# PCB_IGEM.net
KiCad netlist of a schematic drawn in EasyEDA Pro
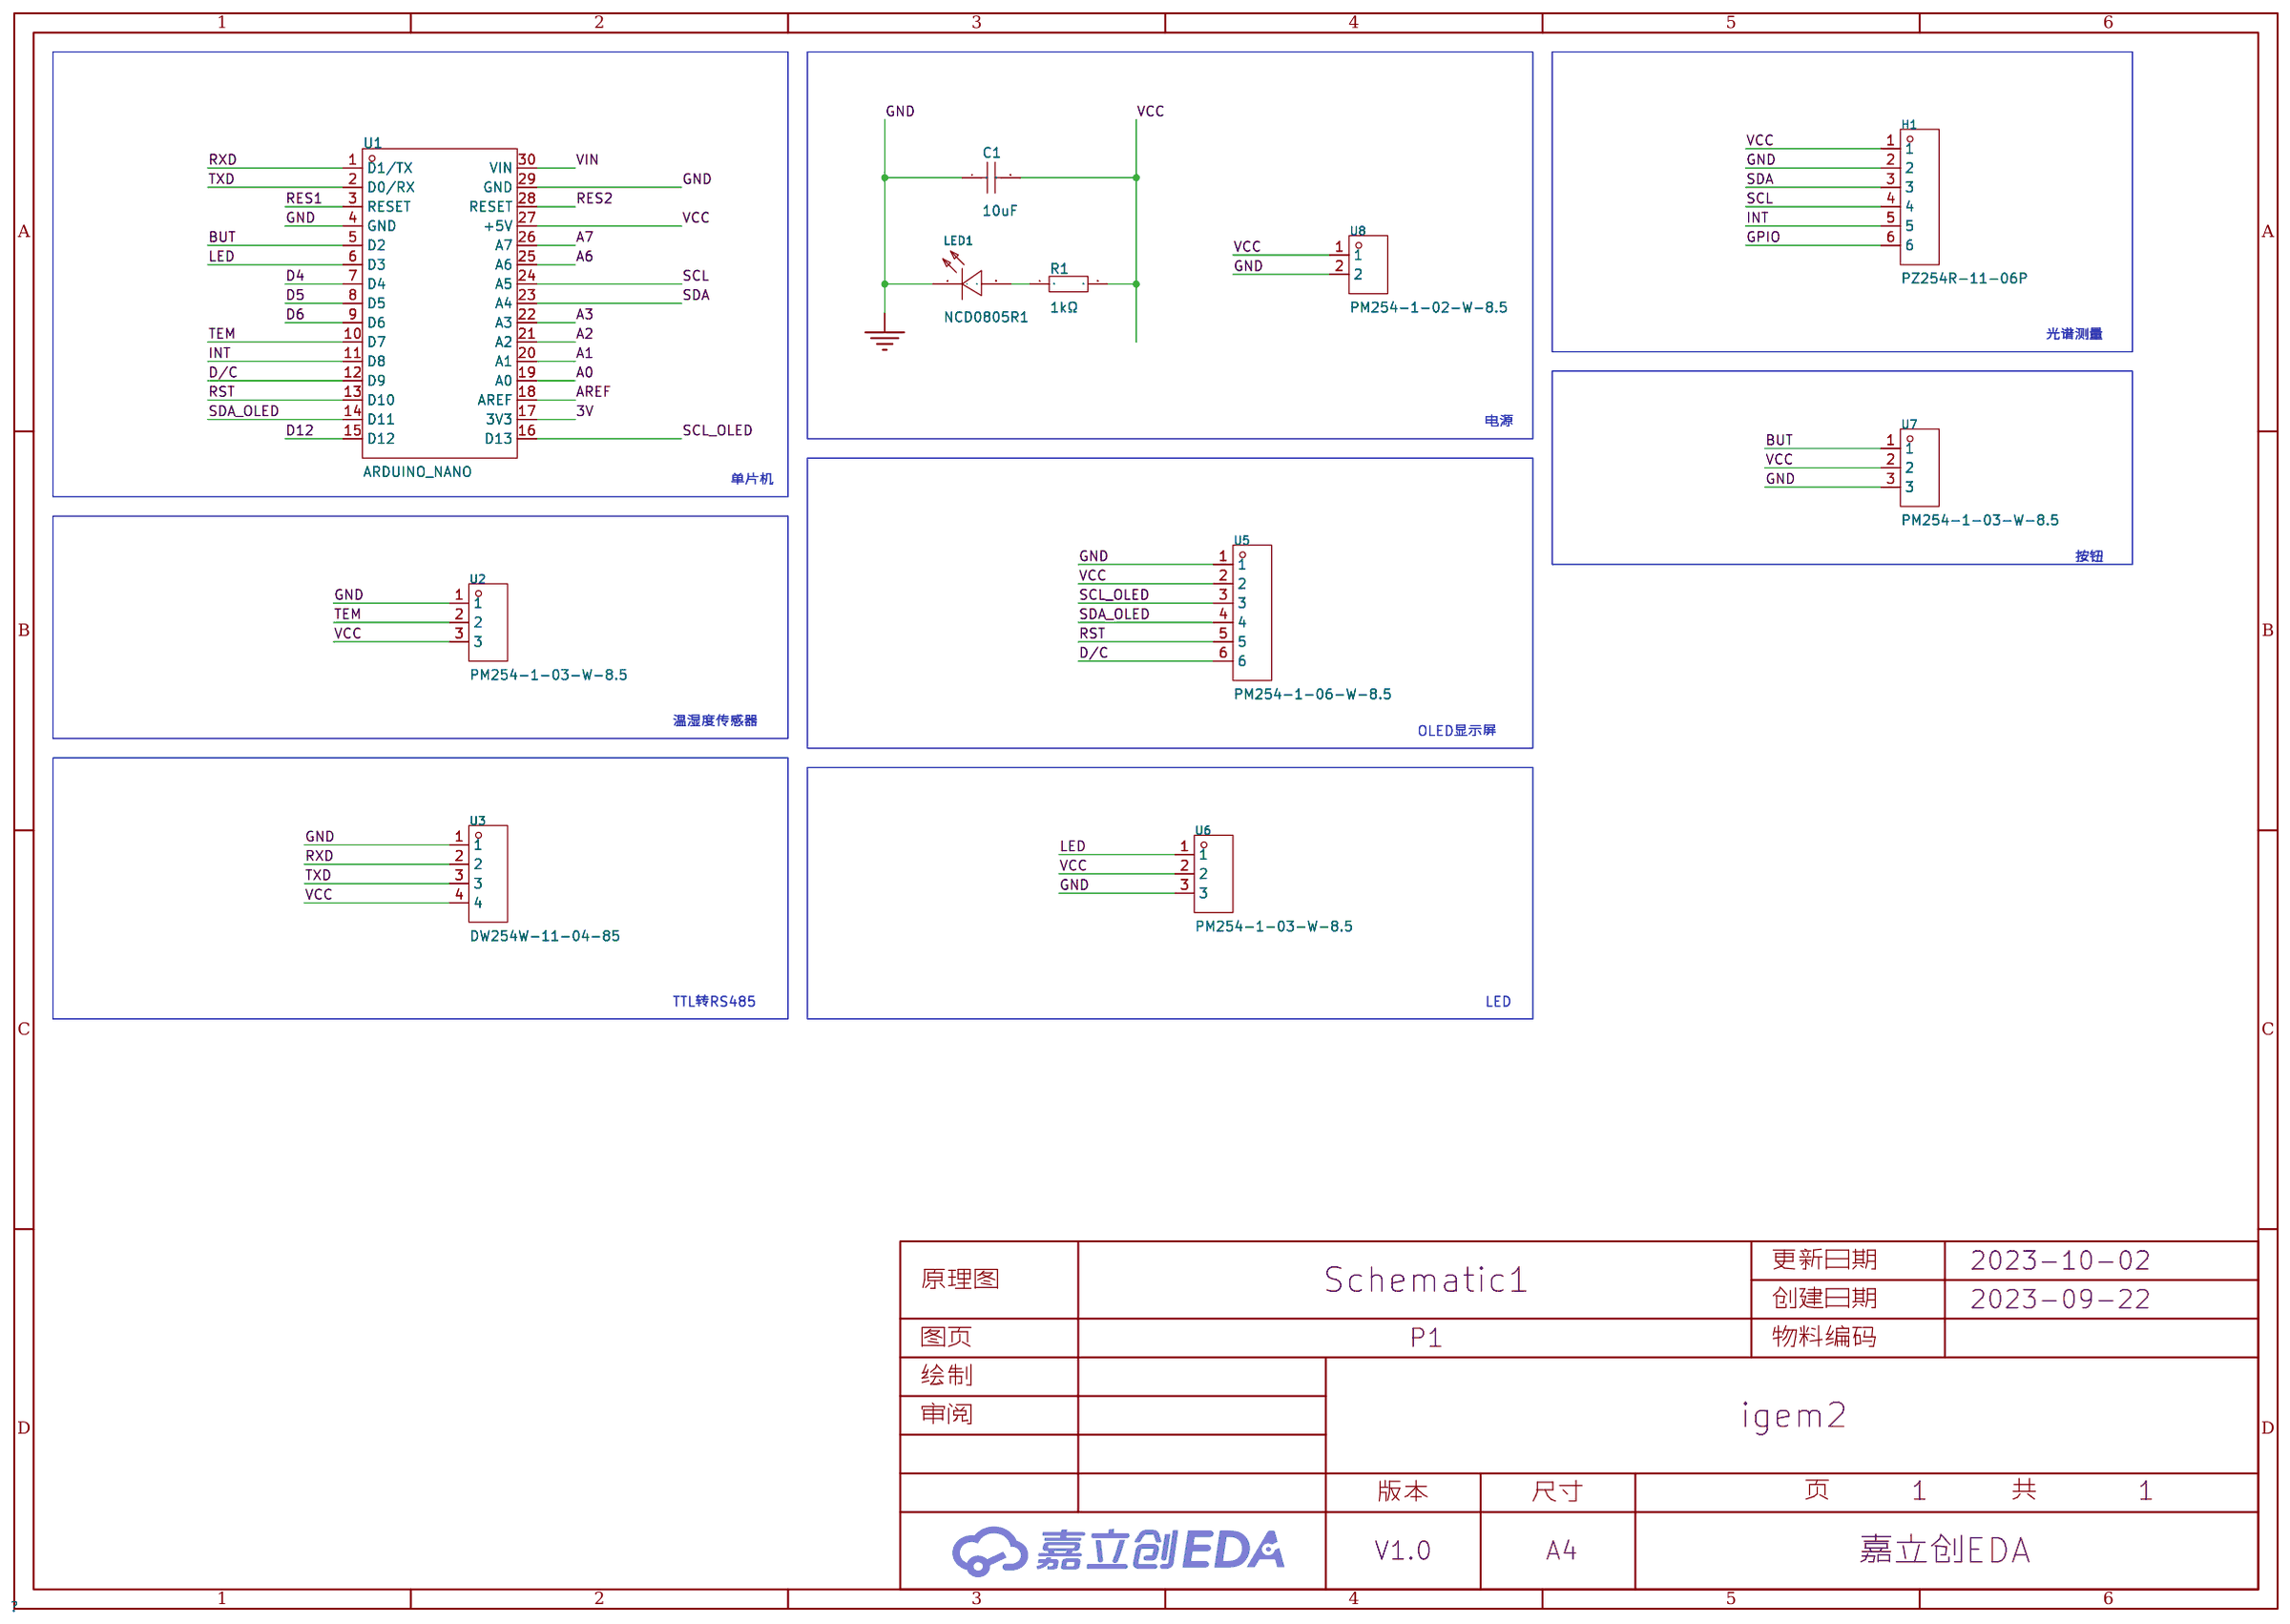
[diagram p0: schematic sheet]

(export (version "E")
  (design (tool "Eeschema 10.0.6"))
  (components
    (comp (ref "C1")
      (value "10uF")
      (footprint "easyedapro:C0805")
      (description "容值:10uF;精度:±10%;额定电压:25V;材质(温度系数):X5R;")
      (fields
        (field (name "Manufacturer Part") "CL21A106KAYNNNE")
        (field (name "Manufacturer") "SAMSUNG(三星)")
      )
      (libsource (lib "easyedapro") (part "CL21A106KAYNNNE"))
    )
    (comp (ref "H1")
      (value "PZ254R-11-06P")
      (footprint "easyedapro:HDR-TH_6P-P2.54-H-M-W10.4")
      (fields (field (name "Manufacturer") "XFCN(兴飞)"))
      (libsource (lib "easyedapro") (part "PZ254R-11-06P"))
    )
    (comp (ref "LED1")
      (value "NCD0805R1")
      (footprint "easyedapro:LED0805-RD_RED")
      (description "发光颜色:红灯;")
      (fields (field (name "Manufacturer") "国星光电"))
      (libsource (lib "easyedapro") (part "FC-2012HRK-620D"))
    )
    (comp (ref "R1")
      (value "1kΩ")
      (footprint "easyedapro:R0805")
      (description "电阻类型:厚膜电阻;阻值:1kΩ;精度:±1%;功率:125mW;")
      (fields
        (field (name "Manufacturer Part") "0805W8F1001T5E")
        (field (name "Manufacturer") "UNI-ROYAL(厚声)")
      )
      (libsource (lib "easyedapro") (part "0805W8F1001T5E"))
    )
    (comp (ref "U1")
      (value "ARDUINO_NANO")
      (footprint "easyedapro:COMM-TH_ARDUINO_NANO")
      (libsource (lib "easyedapro") (part "ARDUINO_NANO"))
    )
    (comp (ref "U2")
      (value "PM254-1-03-W-8.5")
      (footprint "easyedapro:HDR-TH_3P-P2.54-H-F-W10.0-N")
      (fields (field (name "Manufacturer") "HCTL(华灿天禄)"))
      (libsource (lib "easyedapro") (part "PM254-1-03-W-8.5"))
    )
    (comp (ref "U3")
      (value "DW254W-11-04-85")
      (footprint "easyedapro:HDR-TH_4P-P2.54-H-F-W10.3-N")
      (description "排数:单排;总孔位数:4P;间距:2.54mm;插孔结构:1x4P;行距:-;安装类型:弯插;圆孔/方孔:方孔;额定电流:3A;额定电压:-;插孔方向:侧面;塑高:8.5mm;工作温度范围:-;")
      (fields (field (name "Manufacturer") "DEALON(德艺隆)"))
      (libsource (lib "easyedapro") (part "DW254W-11-04-85"))
    )
    (comp (ref "U5")
      (value "PM254-1-06-W-8.5")
      (footprint "easyedapro:HDR-TH_6P-P2.54-H-F-W10.0-N")
      (fields (field (name "Manufacturer") "HCTL(华灿天禄)"))
      (libsource (lib "easyedapro") (part "PM254-1-06-W-8.5"))
    )
    (comp (ref "U6")
      (value "PM254-1-03-W-8.5")
      (footprint "easyedapro:HDR-TH_3P-P2.54-H-F-W10.0-N")
      (fields (field (name "Manufacturer") "HCTL(华灿天禄)"))
      (libsource (lib "easyedapro") (part "PM254-1-03-W-8.5"))
    )
    (comp (ref "U7")
      (value "PM254-1-03-W-8.5")
      (footprint "easyedapro:HDR-TH_3P-P2.54-H-F-W10.0-N")
      (fields (field (name "Manufacturer") "HCTL(华灿天禄)"))
      (libsource (lib "easyedapro") (part "PM254-1-03-W-8.5"))
    )
    (comp (ref "U8")
      (value "PM254-1-02-W-8.5")
      (footprint "easyedapro:HDR-TH_2P-P2.54-H-F-W10.0-N")
      (fields (field (name "Manufacturer") "HCTL(华灿天禄)"))
      (libsource (lib "easyedapro") (part "PM254-1-02-W-8.5"))
    )
  )
  (nets
    (net (code "1") (name "/3V") (class "Default")
      (node (ref "U1") (pin "17") (pinfunction "3V3_17") (pintype "input"))
    )
    (net (code "2") (name "/A0") (class "Default")
      (node (ref "U1") (pin "19") (pinfunction "A0_19") (pintype "input"))
    )
    (net (code "3") (name "/A1") (class "Default")
      (node (ref "U1") (pin "20") (pinfunction "A1_20") (pintype "input"))
    )
    (net (code "4") (name "/A2") (class "Default")
      (node (ref "U1") (pin "21") (pinfunction "A2_21") (pintype "input"))
    )
    (net (code "5") (name "/A3") (class "Default")
      (node (ref "U1") (pin "22") (pinfunction "A3_22") (pintype "input"))
    )
    (net (code "6") (name "/A6") (class "Default")
      (node (ref "U1") (pin "25") (pinfunction "A6_25") (pintype "input"))
    )
    (net (code "7") (name "/A7") (class "Default")
      (node (ref "U1") (pin "26") (pinfunction "A7_26") (pintype "input"))
    )
    (net (code "8") (name "/AREF") (class "Default")
      (node (ref "U1") (pin "18") (pinfunction "AREF_18") (pintype "input"))
    )
    (net (code "9") (name "/BUT") (class "Default")
      (node (ref "U1") (pin "5") (pinfunction "D2_5") (pintype "input"))
      (node (ref "U7") (pin "1") (pinfunction "1_1") (pintype "input"))
    )
    (net (code "10") (name "/D4") (class "Default")
      (node (ref "U1") (pin "7") (pinfunction "D4_7") (pintype "input"))
    )
    (net (code "11") (name "/D5") (class "Default")
      (node (ref "U1") (pin "8") (pinfunction "D5_8") (pintype "input"))
    )
    (net (code "12") (name "/D6") (class "Default")
      (node (ref "U1") (pin "9") (pinfunction "D6_9") (pintype "input"))
    )
    (net (code "13") (name "/D12") (class "Default")
      (node (ref "U1") (pin "15") (pinfunction "D12_15") (pintype "input"))
    )
    (net (code "14") (name "/D{slash}C") (class "Default")
      (node (ref "U1") (pin "12") (pinfunction "D9_12") (pintype "input"))
      (node (ref "U5") (pin "6") (pinfunction "6_6") (pintype "input"))
    )
    (net (code "15") (name "/GPIO") (class "Default")
      (node (ref "H1") (pin "6") (pinfunction "6_6") (pintype "input"))
    )
    (net (code "16") (name "/INT") (class "Default")
      (node (ref "H1") (pin "5") (pinfunction "5_5") (pintype "input"))
      (node (ref "U1") (pin "11") (pinfunction "D8_11") (pintype "input"))
    )
    (net (code "17") (name "/LED") (class "Default")
      (node (ref "U1") (pin "6") (pinfunction "D3_6") (pintype "input"))
      (node (ref "U6") (pin "1") (pinfunction "1_1") (pintype "input"))
    )
    (net (code "18") (name "/RES1") (class "Default")
      (node (ref "U1") (pin "3") (pinfunction "RESET_3") (pintype "input"))
    )
    (net (code "19") (name "/RES2") (class "Default")
      (node (ref "U1") (pin "28") (pinfunction "RESET_28") (pintype "input"))
    )
    (net (code "20") (name "/RST") (class "Default")
      (node (ref "U1") (pin "13") (pinfunction "D10_13") (pintype "input"))
      (node (ref "U5") (pin "5") (pinfunction "5_5") (pintype "input"))
    )
    (net (code "21") (name "/RXD") (class "Default")
      (node (ref "U1") (pin "1") (pinfunction "D1/TX_1") (pintype "input"))
      (node (ref "U3") (pin "2") (pinfunction "2_2") (pintype "input"))
    )
    (net (code "22") (name "/SCL") (class "Default")
      (node (ref "H1") (pin "4") (pinfunction "4_4") (pintype "input"))
      (node (ref "U1") (pin "24") (pinfunction "A5_24") (pintype "input"))
    )
    (net (code "23") (name "/SCL_OLED") (class "Default")
      (node (ref "U1") (pin "16") (pinfunction "D13_16") (pintype "input"))
      (node (ref "U5") (pin "3") (pinfunction "3_3") (pintype "input"))
    )
    (net (code "24") (name "/SDA") (class "Default")
      (node (ref "H1") (pin "3") (pinfunction "3_3") (pintype "input"))
      (node (ref "U1") (pin "23") (pinfunction "A4_23") (pintype "input"))
    )
    (net (code "25") (name "/SDA_OLED") (class "Default")
      (node (ref "U1") (pin "14") (pinfunction "D11_14") (pintype "input"))
      (node (ref "U5") (pin "4") (pinfunction "4_4") (pintype "input"))
    )
    (net (code "26") (name "/TEM") (class "Default")
      (node (ref "U1") (pin "10") (pinfunction "D7_10") (pintype "input"))
      (node (ref "U2") (pin "2") (pinfunction "2_2") (pintype "input"))
    )
    (net (code "27") (name "/TXD") (class "Default")
      (node (ref "U1") (pin "2") (pinfunction "D0/RX_2") (pintype "input"))
      (node (ref "U3") (pin "3") (pinfunction "3_3") (pintype "input"))
    )
    (net (code "28") (name "/VCC") (class "Default")
      (node (ref "C1") (pin "2") (pinfunction "2_2") (pintype "input"))
      (node (ref "H1") (pin "1") (pinfunction "1_1") (pintype "input"))
      (node (ref "R1") (pin "2") (pinfunction "2_2") (pintype "input"))
      (node (ref "U1") (pin "27") (pinfunction "+5V_27") (pintype "input"))
      (node (ref "U2") (pin "3") (pinfunction "3_3") (pintype "input"))
      (node (ref "U3") (pin "4") (pinfunction "4_4") (pintype "input"))
      (node (ref "U5") (pin "2") (pinfunction "2_2") (pintype "input"))
      (node (ref "U6") (pin "2") (pinfunction "2_2") (pintype "input"))
      (node (ref "U7") (pin "2") (pinfunction "2_2") (pintype "input"))
      (node (ref "U8") (pin "1") (pinfunction "1_1") (pintype "input"))
    )
    (net (code "29") (name "/VIN") (class "Default")
      (node (ref "U1") (pin "30") (pinfunction "VIN_30") (pintype "input"))
    )
    (net (code "30") (name "GND") (class "Default")
      (node (ref "C1") (pin "1") (pinfunction "1_1") (pintype "input"))
      (node (ref "H1") (pin "2") (pinfunction "2_2") (pintype "input"))
      (node (ref "LED1") (pin "1") (pinfunction "-_1") (pintype "input"))
      (node (ref "U1") (pin "29") (pinfunction "GND_29") (pintype "input"))
      (node (ref "U1") (pin "4") (pinfunction "GND_4") (pintype "input"))
      (node (ref "U2") (pin "1") (pinfunction "1_1") (pintype "input"))
      (node (ref "U3") (pin "1") (pinfunction "1_1") (pintype "input"))
      (node (ref "U5") (pin "1") (pinfunction "1_1") (pintype "input"))
      (node (ref "U6") (pin "3") (pinfunction "3_3") (pintype "input"))
      (node (ref "U7") (pin "3") (pinfunction "3_3") (pintype "input"))
      (node (ref "U8") (pin "2") (pinfunction "2_2") (pintype "input"))
    )
    (net (code "31") (name "Net-(LED1-+)") (class "Default")
      (node (ref "LED1") (pin "2") (pinfunction "+_2") (pintype "input"))
      (node (ref "R1") (pin "1") (pinfunction "1_1") (pintype "input"))
    )
  )
)
